# node.net
KiCad netlist of a schematic drawn in EAGLE
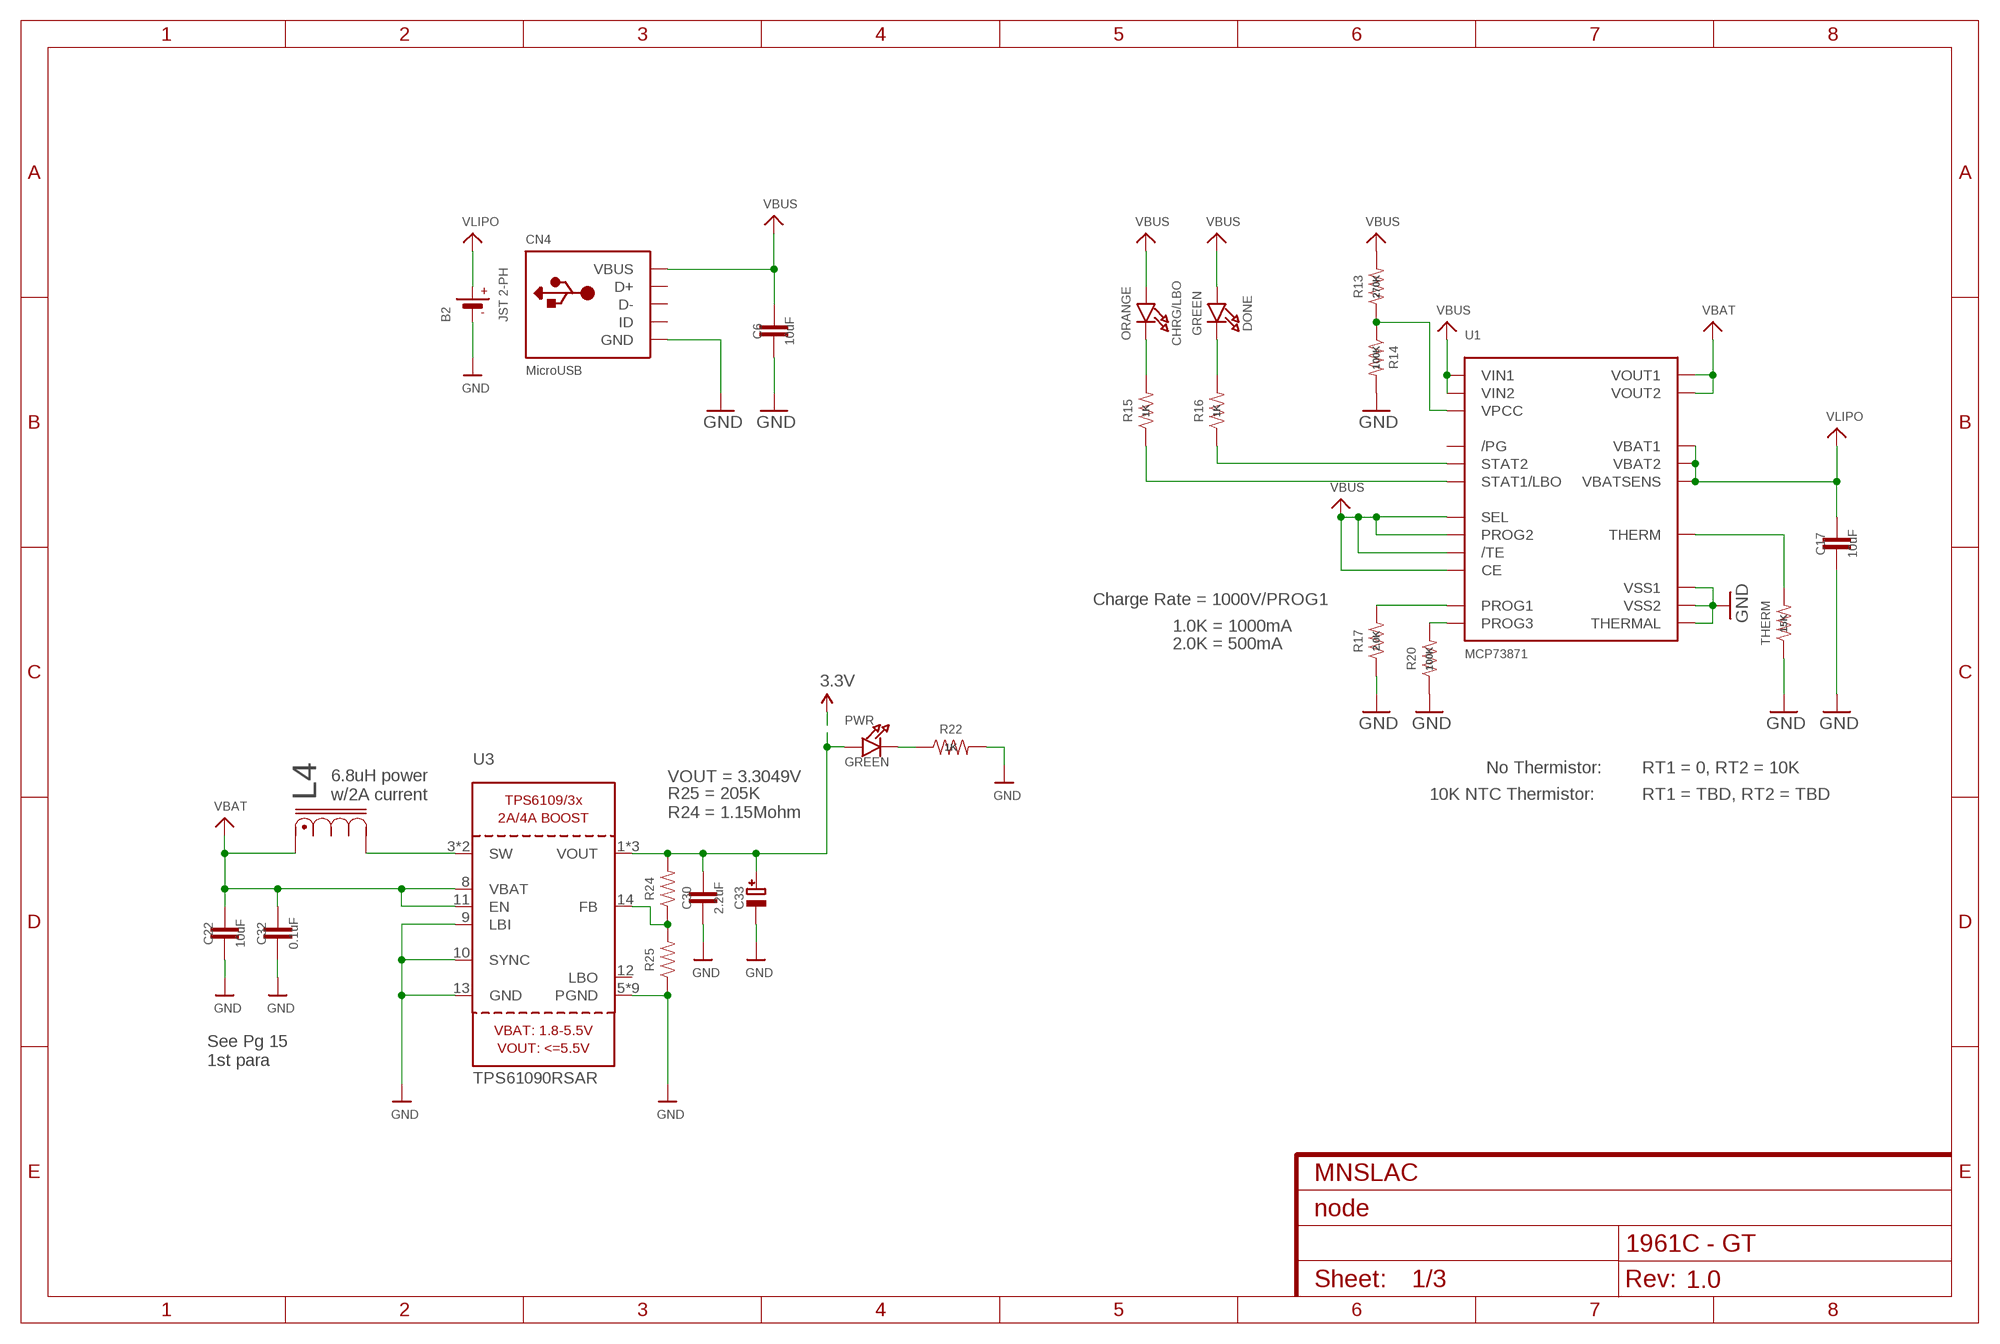
[diagram p0: schematic, sheet 1]
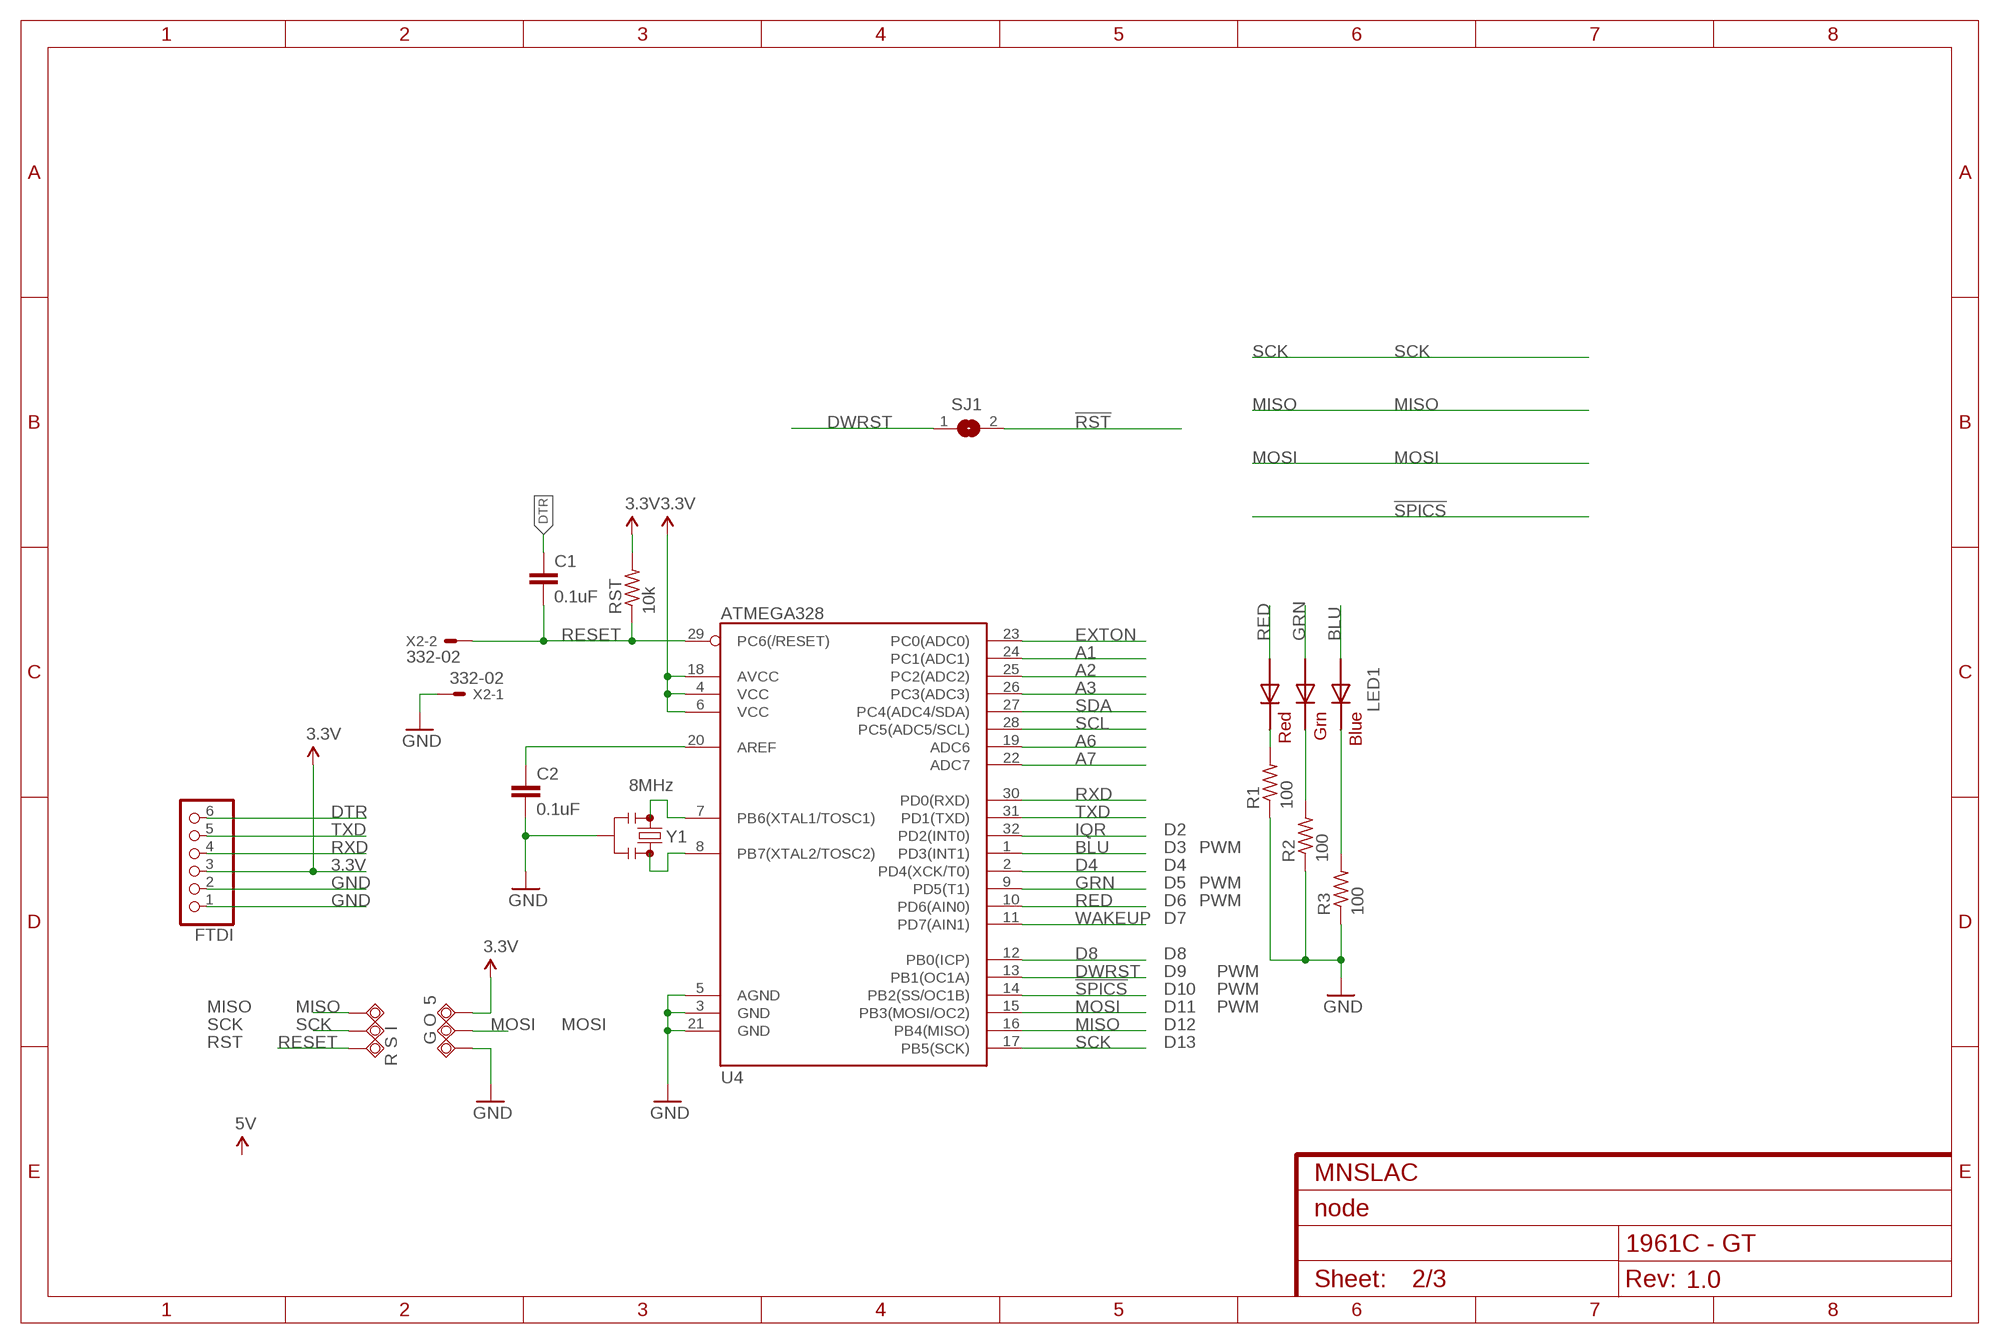
[diagram p1: schematic, sheet 2]
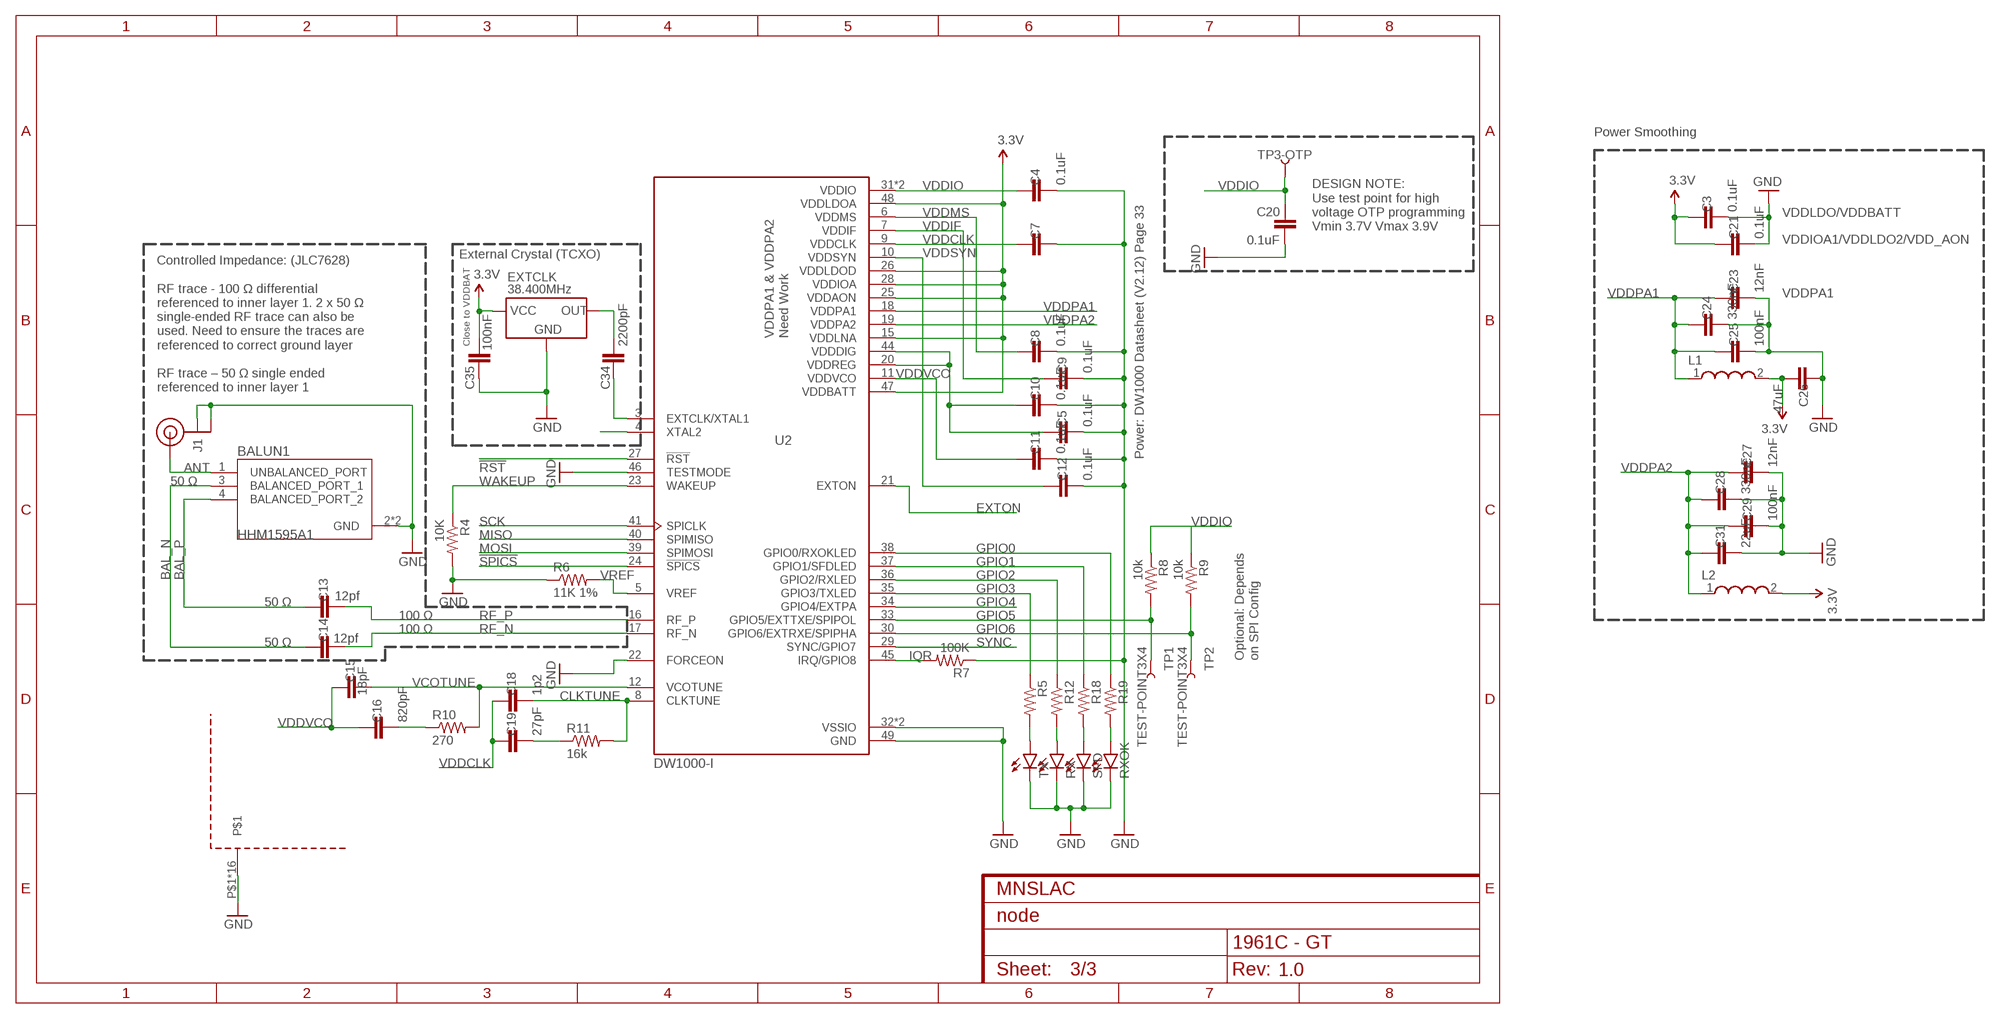
[diagram p2: schematic, sheet 3]

(export (version "E")
  (design (tool "Eeschema 10.0.6"))
  (components
    (comp (ref "BALUN1")
      (value "HHM1595A1")
      (footprint "eagle-import:BALUN_HHM1595A1")
      (fields (field (name "DIGI-KEY_PART_NUMBER") "445-3387-1-ND") (field (name "MF") "TDK"))
      (libsource (lib "eagle-import") (part "HHM1595A1"))
    )
    (comp (ref "C3")
      (value "0.1uF")
      (footprint "eagle-import:0402-CAP")
      (libsource (lib "eagle-import") (part "CAP0402-CAP"))
    )
    (comp (ref "C4")
      (value "0.1uF")
      (footprint "eagle-import:0402-CAP")
      (libsource (lib "eagle-import") (part "CAP0402-CAP"))
    )
    (comp (ref "C5")
      (value "0.1uF")
      (footprint "eagle-import:0402-CAP")
      (libsource (lib "eagle-import") (part "CAP0402-CAP"))
    )
    (comp (ref "C7")
      (value "0.1uF")
      (footprint "eagle-import:0402-CAP")
      (libsource (lib "eagle-import") (part "CAP0402-CAP"))
    )
    (comp (ref "C8")
      (value "0.1uF")
      (footprint "eagle-import:0402-CAP")
      (libsource (lib "eagle-import") (part "CAP0402-CAP"))
    )
    (comp (ref "C9")
      (value "0.1uF")
      (footprint "eagle-import:0402-CAP")
      (libsource (lib "eagle-import") (part "CAP0402-CAP"))
    )
    (comp (ref "C10")
      (value "0.1uF")
      (footprint "eagle-import:0402-CAP")
      (libsource (lib "eagle-import") (part "CAP0402-CAP"))
    )
    (comp (ref "C11")
      (value "0.1uF")
      (footprint "eagle-import:0402-CAP")
      (libsource (lib "eagle-import") (part "CAP0402-CAP"))
    )
    (comp (ref "C12")
      (value "0.1uF")
      (footprint "eagle-import:0402-CAP")
      (libsource (lib "eagle-import") (part "CAP0402-CAP"))
    )
    (comp (ref "C13")
      (value "12pf")
      (footprint "eagle-import:0402-CAP")
      (libsource (lib "eagle-import") (part "CAP0402-CAP"))
    )
    (comp (ref "C14")
      (value "12pf")
      (footprint "eagle-import:0402-CAP")
      (libsource (lib "eagle-import") (part "CAP0402-CAP"))
    )
    (comp (ref "C15")
      (value "18pF")
      (footprint "eagle-import:0402-CAP")
      (libsource (lib "eagle-import") (part "CAP0402-CAP"))
    )
    (comp (ref "C16")
      (value "820pF")
      (footprint "eagle-import:0402-CAP")
      (libsource (lib "eagle-import") (part "CAP0402-CAP"))
    )
    (comp (ref "C18")
      (value "1p2")
      (footprint "eagle-import:0402-CAP")
      (libsource (lib "eagle-import") (part "CAP0402-CAP"))
    )
    (comp (ref "C19")
      (value "27pF")
      (footprint "eagle-import:0402-CAP")
      (libsource (lib "eagle-import") (part "CAP0402-CAP"))
    )
    (comp (ref "C20")
      (value "0.1uF")
      (footprint "eagle-import:0402-CAP")
      (libsource (lib "eagle-import") (part "CAP0402-CAP"))
    )
    (comp (ref "C21")
      (value "0.1uF")
      (footprint "eagle-import:0402-CAP")
      (libsource (lib "eagle-import") (part "CAP0402-CAP"))
    )
    (comp (ref "C23")
      (value "12nF")
      (footprint "eagle-import:0402-CAP")
      (libsource (lib "eagle-import") (part "CAP0402-CAP"))
    )
    (comp (ref "C24")
      (value "330nF")
      (footprint "eagle-import:0402-CAP")
      (libsource (lib "eagle-import") (part "CAP0402-CAP"))
    )
    (comp (ref "C25")
      (value "100nF")
      (footprint "eagle-import:0402-CAP")
      (libsource (lib "eagle-import") (part "CAP0402-CAP"))
    )
    (comp (ref "C26")
      (value "47uF")
      (footprint "eagle-import:0402-CAP")
      (libsource (lib "eagle-import") (part "CAP0402-CAP"))
    )
    (comp (ref "C27")
      (value "12nF")
      (footprint "eagle-import:0402-CAP")
      (libsource (lib "eagle-import") (part "CAP0402-CAP"))
    )
    (comp (ref "C28")
      (value "330nF")
      (footprint "eagle-import:0402-CAP")
      (libsource (lib "eagle-import") (part "CAP0402-CAP"))
    )
    (comp (ref "C29")
      (value "100nF")
      (footprint "eagle-import:0402-CAP")
      (libsource (lib "eagle-import") (part "CAP0402-CAP"))
    )
    (comp (ref "C31")
      (value "22uF")
      (footprint "eagle-import:0402-CAP")
      (libsource (lib "eagle-import") (part "CAP0402-CAP"))
    )
    (comp (ref "C34")
      (value "2200pF")
      (footprint "eagle-import:0402-CAP")
      (libsource (lib "eagle-import") (part "CAP0402-CAP"))
    )
    (comp (ref "C35")
      (value "100nF")
      (footprint "eagle-import:0402-CAP")
      (libsource (lib "eagle-import") (part "CAP0402-CAP"))
    )
    (comp (ref "EXTCLK")
      (value "38.400MHz")
      (footprint "eagle-import:ASTXR-12")
      (libsource (lib "eagle-import") (part "ASTXR-12"))
    )
    (comp (ref "J1")
      (value "U.FL")
      (footprint "eagle-import:U.FL")
      (libsource (lib "eagle-import") (part "ANTENNA_U.FL"))
    )
    (comp (ref "L1")
      (value "BLM15AG601SN1D")
      (footprint "eagle-import:WE-CBA_0402(W=2.2)")
      (libsource (lib "eagle-import") (part "WE-CBA_0402(HC)"))
    )
    (comp (ref "L2")
      (value "BLM15AG601SN1D")
      (footprint "eagle-import:WE-CBA_0402(W=2.2)")
      (libsource (lib "eagle-import") (part "WE-CBA_0402(HC)"))
    )
    (comp (ref "R4")
      (value "10K")
      (footprint "eagle-import:0402-RES")
      (libsource (lib "eagle-import") (part "RESISTOR0402-RES"))
    )
    (comp (ref "R5")
      (value "470")
      (footprint "eagle-import:0402-RES")
      (libsource (lib "eagle-import") (part "RESISTOR0402-RES"))
    )
    (comp (ref "R6")
      (value "11K 1%")
      (footprint "eagle-import:0402-RES")
      (libsource (lib "eagle-import") (part "RESISTOR0402-RES"))
    )
    (comp (ref "R7")
      (value "100K")
      (footprint "eagle-import:0402-RES")
      (libsource (lib "eagle-import") (part "RESISTOR0402-RES"))
    )
    (comp (ref "R8")
      (value "10k")
      (footprint "eagle-import:0402-RES")
      (libsource (lib "eagle-import") (part "RESISTOR0402-RES"))
    )
    (comp (ref "R9")
      (value "10k")
      (footprint "eagle-import:0402-RES")
      (libsource (lib "eagle-import") (part "RESISTOR0402-RES"))
    )
    (comp (ref "R10")
      (value "270")
      (footprint "eagle-import:0402-RES")
      (libsource (lib "eagle-import") (part "RESISTOR0402-RES"))
    )
    (comp (ref "R11")
      (value "16k")
      (footprint "eagle-import:0402-RES")
      (libsource (lib "eagle-import") (part "RESISTOR0402-RES"))
    )
    (comp (ref "R12")
      (value "470")
      (footprint "eagle-import:0402-RES")
      (libsource (lib "eagle-import") (part "RESISTOR0402-RES"))
    )
    (comp (ref "R18")
      (value "470")
      (footprint "eagle-import:0402-RES")
      (libsource (lib "eagle-import") (part "RESISTOR0402-RES"))
    )
    (comp (ref "R19")
      (value "470")
      (footprint "eagle-import:0402-RES")
      (libsource (lib "eagle-import") (part "RESISTOR0402-RES"))
    )
    (comp (ref "RX")
      (value "LED0603")
      (footprint "eagle-import:LED-0603")
      (libsource (lib "eagle-import") (part "LED0603"))
    )
    (comp (ref "RXOK")
      (value "LED0603")
      (footprint "eagle-import:LED-0603")
      (libsource (lib "eagle-import") (part "LED0603"))
    )
    (comp (ref "SFD")
      (value "LED0603")
      (footprint "eagle-import:LED-0603")
      (libsource (lib "eagle-import") (part "LED0603"))
    )
    (comp (ref "TP1")
      (value "TEST-POINT3X4")
      (footprint "eagle-import:PAD.03X.04")
      (libsource (lib "eagle-import") (part "TEST-POINT3X4"))
    )
    (comp (ref "TP2")
      (value "TEST-POINT3X4")
      (footprint "eagle-import:PAD.03X.04")
      (libsource (lib "eagle-import") (part "TEST-POINT3X4"))
    )
    (comp (ref "TP3-OTP")
      (value "TEST-POINT3X4")
      (footprint "eagle-import:PAD.03X.04")
      (libsource (lib "eagle-import") (part "TEST-POINT3X4"))
    )
    (comp (ref "TX")
      (value "LED0603")
      (footprint "eagle-import:LED-0603")
      (libsource (lib "eagle-import") (part "LED0603"))
    )
    (comp (ref "U$6")
      (value "SMS-255F")
      (footprint "eagle-import:SMS-255F")
      (libsource (lib "eagle-import") (part "SMS-255F"))
    )
    (comp (ref "U2")
      (value "DW1000-I")
      (footprint "eagle-import:QFN40P600X600X90-49N")
      (fields (field (name "MF") "Decawave Limited"))
      (libsource (lib "eagle-import") (part "DW1000-I"))
    )
    (comp (ref "B2")
      (value "JST 2-PH")
      (footprint "eagle-import:JSTPH2")
      (libsource (lib "eagle-import") (part "BATTERY"))
    )
    (comp (ref "C6")
      (value "10uF")
      (footprint "eagle-import:0805")
      (libsource (lib "eagle-import") (part "CAP0805"))
    )
    (comp (ref "C17")
      (value "10uF")
      (footprint "eagle-import:0805")
      (libsource (lib "eagle-import") (part "CAP0805"))
    )
    (comp (ref "C22")
      (value "10uF")
      (footprint "eagle-import:0805")
      (libsource (lib "eagle-import") (part "CAP0805"))
    )
    (comp (ref "C30")
      (value "2.2uF")
      (footprint "eagle-import:0805")
      (libsource (lib "eagle-import") (part "CAP0805"))
    )
    (comp (ref "C32")
      (value "0.1uF")
      (footprint "eagle-import:0805")
      (libsource (lib "eagle-import") (part "CAP0805"))
    )
    (comp (ref "C33")
      (value "100uF/6V - https://www.digikey.com/product-detail/en/avx-corporation/F930G107MBA/478-8135-1-ND/4005827")
      (footprint "eagle-import:EIA3528-21_B-R")
      (libsource (lib "eagle-import") (part "CAP_TANTALUMB/3528_REFLOW"))
    )
    (comp (ref "CHRG/LBO")
      (value "ORANGE")
      (footprint "eagle-import:CHIPLED_0805_NOOUTLINE")
      (libsource (lib "eagle-import") (part "LED0805_NOOUTLINE"))
    )
    (comp (ref "CN4")
      (value "MicroUSB")
      (footprint "eagle-import:4UCONN_20329")
      (libsource (lib "eagle-import") (part "USBMICRO_20329"))
    )
    (comp (ref "DONE")
      (value "GREEN")
      (footprint "eagle-import:CHIPLED_0805_NOOUTLINE")
      (libsource (lib "eagle-import") (part "LED0805_NOOUTLINE"))
    )
    (comp (ref "L4")
      (value "https://www.digikey.com/product-detail/en/eaton-electronics-division/DR73-6R8-R/513-1134-1-ND/754632")
      (footprint "eagle-import:DR73")
      (fields (field (name "MANUFACTURER_PART_NUMBER") "DR736R8R"))
      (libsource (lib "eagle-import") (part "DR73-6R8-R"))
    )
    (comp (ref "PWR")
      (value "GREEN")
      (footprint "eagle-import:CHIPLED_0805_NOOUTLINE")
      (libsource (lib "eagle-import") (part "LED0805_NOOUTLINE"))
    )
    (comp (ref "R13")
      (value "270K")
      (footprint "eagle-import:0805")
      (libsource (lib "eagle-import") (part "RESISTOR0805-RES"))
    )
    (comp (ref "R14")
      (value "100K")
      (footprint "eagle-import:0805")
      (libsource (lib "eagle-import") (part "RESISTOR0805-RES"))
    )
    (comp (ref "R15")
      (value "1K")
      (footprint "eagle-import:0805")
      (libsource (lib "eagle-import") (part "RESISTOR0805-RES"))
    )
    (comp (ref "R16")
      (value "1K")
      (footprint "eagle-import:0805")
      (libsource (lib "eagle-import") (part "RESISTOR0805-RES"))
    )
    (comp (ref "R17")
      (value "2.0K")
      (footprint "eagle-import:0805")
      (libsource (lib "eagle-import") (part "RESISTOR0805-RES"))
    )
    (comp (ref "R20")
      (value "100K")
      (footprint "eagle-import:0805")
      (libsource (lib "eagle-import") (part "RESISTOR0805-RES"))
    )
    (comp (ref "R22")
      (value "1K")
      (footprint "eagle-import:0805")
      (libsource (lib "eagle-import") (part "RESISTOR0805-RES"))
    )
    (comp (ref "R24")
      (value "1.15M")
      (footprint "eagle-import:0805")
      (libsource (lib "eagle-import") (part "RESISTOR0805-RES"))
    )
    (comp (ref "R25")
      (value "205K")
      (footprint "eagle-import:0805")
      (libsource (lib "eagle-import") (part "RESISTOR0805-RES"))
    )
    (comp (ref "THERM")
      (value "15K")
      (footprint "eagle-import:0805")
      (libsource (lib "eagle-import") (part "RESISTOR0805-RES"))
    )
    (comp (ref "U1")
      (value "MCP73871")
      (footprint "eagle-import:QFN20_4MM")
      (libsource (lib "eagle-import") (part "MCP73871"))
    )
    (comp (ref "U3")
      (value "TPS61090RSAR")
      (footprint "eagle-import:PVQFN-16")
      (libsource (lib "eagle-import") (part "VREG_TPS6103X"))
    )
    (comp (ref "5")
      (value "TPSQTP08R")
      (footprint "eagle-import:TP08R")
      (libsource (lib "eagle-import") (part "TPSQTP08R"))
    )
    (comp (ref "C1")
      (value "0.1uF")
      (footprint "eagle-import:0805-CAP")
      (libsource (lib "eagle-import") (part "1.0UF-25V-+80/-20(0805){dblquote}"))
    )
    (comp (ref "C2")
      (value "0.1uF")
      (footprint "eagle-import:0805-CAP")
      (libsource (lib "eagle-import") (part "1.0UF-25V-+80/-20(0805){dblquote}"))
    )
    (comp (ref "FTDI")
      (value "PINHD-1X6LOCK")
      (footprint "eagle-import:1X06-BIGLOCK")
      (libsource (lib "eagle-import") (part "PINHD-1X6LOCK"))
    )
    (comp (ref "G")
      (value "TPSQTP08R")
      (footprint "eagle-import:TP08R")
      (libsource (lib "eagle-import") (part "TPSQTP08R"))
    )
    (comp (ref "I")
      (value "TPSQTP08R")
      (footprint "eagle-import:TP08R")
      (libsource (lib "eagle-import") (part "TPSQTP08R"))
    )
    (comp (ref "LED1")
      (value "RGBLED5050")
      (footprint "eagle-import:RGBLED5050")
      (libsource (lib "eagle-import") (part "RGBLED5050"))
    )
    (comp (ref "O")
      (value "TPSQTP08R")
      (footprint "eagle-import:TP08R")
      (libsource (lib "eagle-import") (part "TPSQTP08R"))
    )
    (comp (ref "R")
      (value "TPSQTP08R")
      (footprint "eagle-import:TP08R")
      (libsource (lib "eagle-import") (part "TPSQTP08R"))
    )
    (comp (ref "R1")
      (value "100")
      (footprint "eagle-import:R0805")
      (libsource (lib "eagle-import") (part "R-US_R0805"))
    )
    (comp (ref "R2")
      (value "100")
      (footprint "eagle-import:R0805")
      (libsource (lib "eagle-import") (part "R-US_R0805"))
    )
    (comp (ref "R3")
      (value "100")
      (footprint "eagle-import:R0805")
      (libsource (lib "eagle-import") (part "R-US_R0805"))
    )
    (comp (ref "RST")
      (value "10k")
      (footprint "eagle-import:R0805")
      (libsource (lib "eagle-import") (part "R-US_R0805"))
    )
    (comp (ref "S")
      (value "TPSQTP08R")
      (footprint "eagle-import:TP08R")
      (libsource (lib "eagle-import") (part "TPSQTP08R"))
    )
    (comp (ref "SJ1") (value "SJ") (footprint "eagle-import:SJ") (libsource (lib "eagle-import") (part "SJ")))
    (comp (ref "U4")
      (value "ATMEGA328")
      (footprint "eagle-import:TQFP32-08")
      (libsource (lib "eagle-import") (part "ATMEGA168"))
    )
    (comp (ref "X2")
      (value "332-02")
      (footprint "eagle-import:332-02")
      (libsource (lib "eagle-import") (part "332-02"))
    )
    (comp (ref "Y1")
      (value "8MHz")
      (footprint "eagle-import:RESONATOR-SMD_MED")
      (libsource (lib "eagle-import") (part "RESONATOR4MHZ"))
    )
  )
  (nets
    (net (code "1") (name "3.3V") (class "Default")
      (node (ref "5") (pin "TP") (pinfunction "TP_TP") (pintype "input"))
      (node (ref "C21") (pin "1") (pinfunction "1_1") (pintype "passive"))
      (node (ref "C26") (pin "2") (pinfunction "2_2") (pintype "passive"))
      (node (ref "C3") (pin "1") (pinfunction "1_1") (pintype "passive"))
      (node (ref "C30") (pin "1") (pinfunction "1_1") (pintype "passive"))
      (node (ref "C33") (pin "+") (pinfunction "+_+") (pintype "passive"))
      (node (ref "C35") (pin "2") (pinfunction "2_2") (pintype "passive"))
      (node (ref "EXTCLK") (pin "P$6") (pinfunction "VCC_P$6") (pintype "bidirectional"))
      (node (ref "FTDI") (pin "3") (pinfunction "3_3") (pintype "passive"))
      (node (ref "L1") (pin "2") (pinfunction "2_2") (pintype "passive"))
      (node (ref "L2") (pin "2") (pinfunction "2_2") (pintype "passive"))
      (node (ref "PWR") (pin "A") (pinfunction "A_A") (pintype "passive"))
      (node (ref "R24") (pin "2") (pinfunction "2_2") (pintype "passive"))
      (node (ref "RST") (pin "2") (pinfunction "2_2") (pintype "passive"))
      (node (ref "U2") (pin "15") (pinfunction "VDDLNA_15") (pintype "power_in"))
      (node (ref "U2") (pin "25") (pinfunction "VDDAON_25") (pintype "power_in"))
      (node (ref "U2") (pin "26") (pinfunction "VDDLDOD_26") (pintype "power_in"))
      (node (ref "U2") (pin "28") (pinfunction "VDDIOA_28") (pintype "power_in"))
      (node (ref "U2") (pin "47") (pinfunction "VDDBATT_47") (pintype "power_in"))
      (node (ref "U2") (pin "48") (pinfunction "VDDLDOA_48") (pintype "power_in"))
      (node (ref "U3") (pin "1") (pinfunction "VOUT_1") (pintype "power_in"))
      (node (ref "U3") (pin "15") (pinfunction "VOUT_15") (pintype "power_in"))
      (node (ref "U3") (pin "16") (pinfunction "VOUT_16") (pintype "power_in"))
      (node (ref "U4") (pin "18") (pinfunction "AVCC_18") (pintype "bidirectional"))
      (node (ref "U4") (pin "4") (pinfunction "VCC_4") (pintype "bidirectional"))
      (node (ref "U4") (pin "6") (pinfunction "VCC_6") (pintype "bidirectional"))
    )
    (net (code "3") (name "A1") (class "Default")
      (node (ref "U4") (pin "24") (pinfunction "PC1(ADC1)_24") (pintype "bidirectional"))
    )
    (net (code "4") (name "A2") (class "Default")
      (node (ref "U4") (pin "25") (pinfunction "PC2(ADC2)_25") (pintype "bidirectional"))
    )
    (net (code "5") (name "A3") (class "Default")
      (node (ref "U4") (pin "26") (pinfunction "PC3(ADC3)_26") (pintype "bidirectional"))
    )
    (net (code "6") (name "A6") (class "Default")
      (node (ref "U4") (pin "19") (pinfunction "ADC6_19") (pintype "bidirectional"))
    )
    (net (code "7") (name "A7") (class "Default")
      (node (ref "U4") (pin "22") (pinfunction "ADC7_22") (pintype "bidirectional"))
    )
    (net (code "8") (name "ANT") (class "Default")
      (node (ref "BALUN1") (pin "1") (pinfunction "UNBALANCED_PORT_1") (pintype "bidirectional"))
      (node (ref "J1") (pin "3") (pinfunction "SIGNAL_3") (pintype "passive"))
    )
    (net (code "9") (name "BAL_N") (class "Default")
      (node (ref "BALUN1") (pin "3") (pinfunction "BALANCED_PORT_1_3") (pintype "bidirectional"))
      (node (ref "C14") (pin "1") (pinfunction "1_1") (pintype "passive"))
    )
    (net (code "10") (name "BAL_P") (class "Default")
      (node (ref "BALUN1") (pin "4") (pinfunction "BALANCED_PORT_2_4") (pintype "bidirectional"))
      (node (ref "C13") (pin "1") (pinfunction "1_1") (pintype "passive"))
    )
    (net (code "11") (name "BLU") (class "Default")
      (node (ref "LED1") (pin "3") (pinfunction "BLUE_A_3") (pintype "bidirectional"))
      (node (ref "U4") (pin "1") (pinfunction "PD3(INT1)_1") (pintype "bidirectional"))
    )
    (net (code "12") (name "CLKTUNE") (class "Default")
      (node (ref "C18") (pin "2") (pinfunction "2_2") (pintype "passive"))
      (node (ref "R11") (pin "2") (pinfunction "2_2") (pintype "passive"))
      (node (ref "U2") (pin "8") (pinfunction "CLKTUNE_8") (pintype "bidirectional"))
    )
    (net (code "13") (name "D4") (class "Default")
      (node (ref "U4") (pin "2") (pinfunction "PD4(XCK/T0)_2") (pintype "bidirectional"))
    )
    (net (code "14") (name "D8") (class "Default")
      (node (ref "U4") (pin "12") (pinfunction "PB0(ICP)_12") (pintype "bidirectional"))
    )
    (net (code "15") (name "DTR") (class "Default")
      (node (ref "C1") (pin "1") (pinfunction "1_1") (pintype "passive"))
      (node (ref "FTDI") (pin "6") (pinfunction "6_6") (pintype "passive"))
    )
    (net (code "16") (name "DWRST") (class "Default")
      (node (ref "SJ1") (pin "1") (pinfunction "1_1") (pintype "passive"))
      (node (ref "U4") (pin "13") (pinfunction "PB1(OC1A)_13") (pintype "bidirectional"))
    )
    (net (code "17") (name "EXTON") (class "Default")
      (node (ref "U2") (pin "21") (pinfunction "EXTON_21") (pintype "output"))
      (node (ref "U4") (pin "23") (pinfunction "PC0(ADC0)_23") (pintype "bidirectional"))
    )
    (net (code "18") (name "GND") (class "Default")
      (node (ref "B2") (pin "1") (pinfunction "-_1") (pintype "passive"))
      (node (ref "BALUN1") (pin "2") (pinfunction "GND_2") (pintype "power_in"))
      (node (ref "BALUN1") (pin "5") (pinfunction "GND_5") (pintype "power_in"))
      (node (ref "C10") (pin "2") (pinfunction "2_2") (pintype "passive"))
      (node (ref "C11") (pin "2") (pinfunction "2_2") (pintype "passive"))
      (node (ref "C12") (pin "2") (pinfunction "2_2") (pintype "passive"))
      (node (ref "C17") (pin "2") (pinfunction "2_2") (pintype "passive"))
      (node (ref "C2") (pin "2") (pinfunction "2_2") (pintype "passive"))
      (node (ref "C20") (pin "1") (pinfunction "1_1") (pintype "passive"))
      (node (ref "C21") (pin "2") (pinfunction "2_2") (pintype "passive"))
      (node (ref "C22") (pin "2") (pinfunction "2_2") (pintype "passive"))
      (node (ref "C23") (pin "2") (pinfunction "2_2") (pintype "passive"))
      (node (ref "C24") (pin "2") (pinfunction "2_2") (pintype "passive"))
      (node (ref "C25") (pin "2") (pinfunction "2_2") (pintype "passive"))
      (node (ref "C26") (pin "1") (pinfunction "1_1") (pintype "passive"))
      (node (ref "C27") (pin "2") (pinfunction "2_2") (pintype "passive"))
      (node (ref "C28") (pin "2") (pinfunction "2_2") (pintype "passive"))
      (node (ref "C29") (pin "2") (pinfunction "2_2") (pintype "passive"))
      (node (ref "C3") (pin "2") (pinfunction "2_2") (pintype "passive"))
      (node (ref "C30") (pin "2") (pinfunction "2_2") (pintype "passive"))
      (node (ref "C31") (pin "2") (pinfunction "2_2") (pintype "passive"))
      (node (ref "C32") (pin "2") (pinfunction "2_2") (pintype "passive"))
      (node (ref "C33") (pin "-") (pinfunction "-_-") (pintype "passive"))
      (node (ref "C35") (pin "1") (pinfunction "1_1") (pintype "passive"))
      (node (ref "C4") (pin "2") (pinfunction "2_2") (pintype "passive"))
      (node (ref "C5") (pin "2") (pinfunction "2_2") (pintype "passive"))
      (node (ref "C6") (pin "2") (pinfunction "2_2") (pintype "passive"))
      (node (ref "C7") (pin "2") (pinfunction "2_2") (pintype "passive"))
      (node (ref "C8") (pin "2") (pinfunction "2_2") (pintype "passive"))
      (node (ref "C9") (pin "2") (pinfunction "2_2") (pintype "passive"))
      (node (ref "CN4") (pin "BASE@1") (pinfunction "GND_BASE@1") (pintype "power_in"))
      (node (ref "CN4") (pin "BASE@2") (pinfunction "GND_BASE@2") (pintype "power_in"))
      (node (ref "CN4") (pin "GND") (pinfunction "GND_GND") (pintype "power_in"))
      (node (ref "CN4") (pin "SPRT@1") (pinfunction "GND_SPRT@1") (pintype "power_in"))
      (node (ref "CN4") (pin "SPRT@2") (pinfunction "GND_SPRT@2") (pintype "power_in"))
      (node (ref "CN4") (pin "SPRT@3") (pinfunction "GND_SPRT@3") (pintype "power_in"))
      (node (ref "CN4") (pin "SPRT@4") (pinfunction "GND_SPRT@4") (pintype "power_in"))
      (node (ref "EXTCLK") (pin "P$1") (pinfunction "GND_P$1") (pintype "bidirectional"))
      (node (ref "EXTCLK") (pin "P$3") (pinfunction "GND_P$3") (pintype "bidirectional"))
      (node (ref "FTDI") (pin "1") (pinfunction "1_1") (pintype "passive"))
      (node (ref "FTDI") (pin "2") (pinfunction "2_2") (pintype "passive"))
      (node (ref "G") (pin "TP") (pinfunction "TP_TP") (pintype "input"))
      (node (ref "J1") (pin "1") (pinfunction "GND_1") (pintype "passive"))
      (node (ref "J1") (pin "2") (pinfunction "GND_2") (pintype "passive"))
      (node (ref "R1") (pin "1") (pinfunction "1_1") (pintype "passive"))
      (node (ref "R14") (pin "2") (pinfunction "2_2") (pintype "passive"))
      (node (ref "R17") (pin "1") (pinfunction "1_1") (pintype "passive"))
      (node (ref "R2") (pin "1") (pinfunction "1_1") (pintype "passive"))
      (node (ref "R20") (pin "1") (pinfunction "1_1") (pintype "passive"))
      (node (ref "R22") (pin "2") (pinfunction "2_2") (pintype "passive"))
      (node (ref "R25") (pin "1") (pinfunction "1_1") (pintype "passive"))
      (node (ref "R3") (pin "1") (pinfunction "1_1") (pintype "passive"))
      (node (ref "R4") (pin "2") (pinfunction "2_2") (pintype "passive"))
      (node (ref "R6") (pin "1") (pinfunction "1_1") (pintype "passive"))
      (node (ref "R7") (pin "1") (pinfunction "1_1") (pintype "passive"))
      (node (ref "RX") (pin "C") (pinfunction "C_C") (pintype "passive"))
      (node (ref "RXOK") (pin "C") (pinfunction "C_C") (pintype "passive"))
      (node (ref "SFD") (pin "C") (pinfunction "C_C") (pintype "passive"))
      (node (ref "THERM") (pin "1") (pinfunction "1_1") (pintype "passive"))
      (node (ref "TX") (pin "C") (pinfunction "C_C") (pintype "passive"))
      (node (ref "U$6") (pin "P$1") (pinfunction "P$1_P$1") (pintype "bidirectional"))
      (node (ref "U$6") (pin "P$10") (pinfunction "P$1_P$10") (pintype "bidirectional"))
      (node (ref "U$6") (pin "P$11") (pinfunction "P$1_P$11") (pintype "bidirectional"))
      (node (ref "U$6") (pin "P$12") (pinfunction "P$1_P$12") (pintype "bidirectional"))
      (node (ref "U$6") (pin "P$13") (pinfunction "P$1_P$13") (pintype "bidirectional"))
      (node (ref "U$6") (pin "P$14") (pinfunction "P$1_P$14") (pintype "bidirectional"))
      (node (ref "U$6") (pin "P$15") (pinfunction "P$1_P$15") (pintype "bidirectional"))
      (node (ref "U$6") (pin "P$16") (pinfunction "P$1_P$16") (pintype "bidirectional"))
      (node (ref "U$6") (pin "P$2") (pinfunction "P$1_P$2") (pintype "bidirectional"))
      (node (ref "U$6") (pin "P$3") (pinfunction "P$1_P$3") (pintype "bidirectional"))
      (node (ref "U$6") (pin "P$4") (pinfunction "P$1_P$4") (pintype "bidirectional"))
      (node (ref "U$6") (pin "P$5") (pinfunction "P$1_P$5") (pintype "bidirectional"))
      (node (ref "U$6") (pin "P$6") (pinfunction "P$1_P$6") (pintype "bidirectional"))
      (node (ref "U$6") (pin "P$7") (pinfunction "P$1_P$7") (pintype "bidirectional"))
      (node (ref "U$6") (pin "P$8") (pinfunction "P$1_P$8") (pintype "bidirectional"))
      (node (ref "U$6") (pin "P$9") (pinfunction "P$1_P$9") (pintype "bidirectional"))
      (node (ref "U1") (pin "P$10") (pinfunction "VSS1_P$10") (pintype "bidirectional"))
      (node (ref "U1") (pin "P$11") (pinfunction "VSS2_P$11") (pintype "bidirectional"))
      (node (ref "U1") (pin "P$21") (pinfunction "THERMAL_P$21") (pintype "bidirectional"))
      (node (ref "U2") (pin "22") (pinfunction "FORCEON_22") (pintype "bidirectional"))
      (node (ref "U2") (pin "32") (pinfunction "VSSIO_32") (pintype "power_in"))
      (node (ref "U2") (pin "43") (pinfunction "VSSIO_43") (pintype "power_in"))
      (node (ref "U2") (pin "46") (pinfunction "TESTMODE_46") (pintype "input"))
      (node (ref "U2") (pin "49") (pinfunction "GND_49") (pintype "power_in"))
      (node (ref "U3") (pin "10") (pinfunction "SYNC_10") (pintype "input"))
      (node (ref "U3") (pin "13") (pinfunction "GND_13") (pintype "power_in"))
      (node (ref "U3") (pin "5") (pinfunction "PGND_5") (pintype "power_in"))
      (node (ref "U3") (pin "6") (pinfunction "PGND_6") (pintype "power_in"))
      (node (ref "U3") (pin "7") (pinfunction "PGND_7") (pintype "power_in"))
      (node (ref "U3") (pin "9") (pinfunction "LBI_9") (pintype "input"))
      (node (ref "U3") (pin "P$18") (pinfunction "PGND_P$18") (pintype "power_in"))
      (node (ref "U3") (pin "P$19") (pinfunction "PGND_P$19") (pintype "power_in"))
      (node (ref "U3") (pin "P$20") (pinfunction "PGND_P$20") (pintype "power_in"))
      (node (ref "U3") (pin "P$21") (pinfunction "PGND_P$21") (pintype "power_in"))
      (node (ref "U3") (pin "P$22") (pinfunction "PGND_P$22") (pintype "power_in"))
      (node (ref "U3") (pin "THERMAL") (pinfunction "PGND_THERMAL") (pintype "power_in"))
      (node (ref "U4") (pin "21") (pinfunction "GND_21") (pintype "bidirectional"))
      (node (ref "U4") (pin "3") (pinfunction "GND_3") (pintype "bidirectional"))
      (node (ref "U4") (pin "5") (pinfunction "AGND_5") (pintype "bidirectional"))
      (node (ref "X2") (pin "1") (pinfunction "S_1") (pintype "passive"))
      (node (ref "Y1") (pin "2") (pinfunction "2_2") (pintype "passive"))
    )
    (net (code "19") (name "GPIO0") (class "Default")
      (node (ref "R19") (pin "1") (pinfunction "1_1") (pintype "passive"))
      (node (ref "U2") (pin "38") (pinfunction "GPIO0/RXOKLED_38") (pintype "bidirectional"))
    )
    (net (code "20") (name "GPIO1") (class "Default")
      (node (ref "R18") (pin "1") (pinfunction "1_1") (pintype "passive"))
      (node (ref "U2") (pin "37") (pinfunction "GPIO1/SFDLED_37") (pintype "bidirectional"))
    )
    (net (code "21") (name "GPIO2") (class "Default")
      (node (ref "R12") (pin "1") (pinfunction "1_1") (pintype "passive"))
      (node (ref "U2") (pin "36") (pinfunction "GPIO2/RXLED_36") (pintype "bidirectional"))
    )
    (net (code "22") (name "GPIO3") (class "Default")
      (node (ref "R5") (pin "1") (pinfunction "1_1") (pintype "passive"))
      (node (ref "U2") (pin "35") (pinfunction "GPIO3/TXLED_35") (pintype "bidirectional"))
    )
    (net (code "23") (name "GPIO4") (class "Default")
      (node (ref "U2") (pin "34") (pinfunction "GPIO4/EXTPA_34") (pintype "bidirectional"))
    )
    (net (code "24") (name "GPIO5") (class "Default")
      (node (ref "R8") (pin "2") (pinfunction "2_2") (pintype "passive"))
      (node (ref "TP1") (pin "P$1") (pinfunction "1_P$1") (pintype "bidirectional"))
      (node (ref "U2") (pin "33") (pinfunction "GPIO5/EXTTXE/SPIPOL_33") (pintype "bidirectional"))
    )
    (net (code "25") (name "GPIO6") (class "Default")
      (node (ref "R9") (pin "2") (pinfunction "2_2") (pintype "passive"))
      (node (ref "TP2") (pin "P$1") (pinfunction "1_P$1") (pintype "bidirectional"))
      (node (ref "U2") (pin "30") (pinfunction "GPIO6/EXTRXE/SPIPHA_30") (pintype "bidirectional"))
    )
    (net (code "26") (name "GRN") (class "Default")
      (node (ref "LED1") (pin "1") (pinfunction "GREEN_A_1") (pintype "bidirectional"))
      (node (ref "U4") (pin "9") (pinfunction "PD5(T1)_9") (pintype "bidirectional"))
    )
    (net (code "27") (name "IQR") (class "Default")
      (node (ref "R7") (pin "2") (pinfunction "2_2") (pintype "passive"))
      (node (ref "U2") (pin "45") (pinfunction "IRQ/GPIO8_45") (pintype "bidirectional"))
      (node (ref "U4") (pin "32") (pinfunction "PD2(INT0)_32") (pintype "bidirectional"))
    )
    (net (code "28") (name "MISO") (class "Default")
      (node (ref "I") (pin "TP") (pinfunction "TP_TP") (pintype "input"))
      (node (ref "U2") (pin "40") (pinfunction "SPIMISO_40") (pintype "output"))
      (node (ref "U4") (pin "16") (pinfunction "PB4(MISO)_16") (pintype "bidirectional"))
    )
    (net (code "29") (name "MOSI") (class "Default")
      (node (ref "O") (pin "TP") (pinfunction "TP_TP") (pintype "input"))
      (node (ref "U2") (pin "39") (pinfunction "SPIMOSI_39") (pintype "input"))
      (node (ref "U4") (pin "15") (pinfunction "PB3(MOSI/OC2)_15") (pintype "bidirectional"))
    )
    (net (code "30") (name "Net-(C16-Pad2)") (class "Default")
      (node (ref "C16") (pin "2") (pinfunction "2_2") (pintype "passive"))
      (node (ref "R10") (pin "1") (pinfunction "1_1") (pintype "passive"))
    )
    (net (code "31") (name "Net-(C19-Pad2)") (class "Default")
      (node (ref "C19") (pin "2") (pinfunction "2_2") (pintype "passive"))
      (node (ref "R11") (pin "1") (pinfunction "1_1") (pintype "passive"))
    )
    (net (code "32") (name "Net-(CHRG/LBO-PadC)") (class "Default")
      (node (ref "CHRG/LBO") (pin "C") (pinfunction "C_C") (pintype "passive"))
      (node (ref "R15") (pin "2") (pinfunction "2_2") (pintype "passive"))
    )
    (net (code "33") (name "Net-(DONE-PadC)") (class "Default")
      (node (ref "DONE") (pin "C") (pinfunction "C_C") (pintype "passive"))
      (node (ref "R16") (pin "2") (pinfunction "2_2") (pintype "passive"))
    )
    (net (code "34") (name "Net-(EXTCLK-OUT)") (class "Default")
      (node (ref "C34") (pin "2") (pinfunction "2_2") (pintype "passive"))
      (node (ref "EXTCLK") (pin "P$4") (pinfunction "OUT_P$4") (pintype "bidirectional"))
    )
    (net (code "35") (name "Net-(L4-Pad2)") (class "Default")
      (node (ref "L4") (pin "2") (pinfunction "2_2") (pintype "passive"))
      (node (ref "U3") (pin "3") (pinfunction "SW_3") (pintype "input"))
      (node (ref "U3") (pin "4") (pinfunction "SW_4") (pintype "input"))
    )
    (net (code "36") (name "Net-(LED1-BLUE_C)") (class "Default")
      (node (ref "LED1") (pin "4") (pinfunction "BLUE_C_4") (pintype "bidirectional"))
      (node (ref "R3") (pin "2") (pinfunction "2_2") (pintype "passive"))
    )
    (net (code "37") (name "Net-(LED1-GREEN_C)") (class "Default")
      (node (ref "LED1") (pin "6") (pinfunction "GREEN_C_6") (pintype "bidirectional"))
      (node (ref "R2") (pin "2") (pinfunction "2_2") (pintype "passive"))
    )
    (net (code "38") (name "Net-(LED1-RED_C)") (class "Default")
      (node (ref "LED1") (pin "5") (pinfunction "RED_C_5") (pintype "bidirectional"))
      (node (ref "R1") (pin "2") (pinfunction "2_2") (pintype "passive"))
    )
    (net (code "39") (name "Net-(PWR-PadC)") (class "Default")
      (node (ref "PWR") (pin "C") (pinfunction "C_C") (pintype "passive"))
      (node (ref "R22") (pin "1") (pinfunction "1_1") (pintype "passive"))
    )
    (net (code "40") (name "Net-(R5-Pad2)") (class "Default")
      (node (ref "R5") (pin "2") (pinfunction "2_2") (pintype "passive"))
      (node (ref "TX") (pin "A") (pinfunction "A_A") (pintype "passive"))
    )
    (net (code "41") (name "Net-(R12-Pad2)") (class "Default")
      (node (ref "R12") (pin "2") (pinfunction "2_2") (pintype "passive"))
      (node (ref "RX") (pin "A") (pinfunction "A_A") (pintype "passive"))
    )
    (net (code "42") (name "Net-(R18-Pad2)") (class "Default")
      (node (ref "R18") (pin "2") (pinfunction "2_2") (pintype "passive"))
      (node (ref "SFD") (pin "A") (pinfunction "A_A") (pintype "passive"))
    )
    (net (code "43") (name "Net-(R19-Pad2)") (class "Default")
      (node (ref "R19") (pin "2") (pinfunction "2_2") (pintype "passive"))
      (node (ref "RXOK") (pin "A") (pinfunction "A_A") (pintype "passive"))
    )
    (net (code "44") (name "Net-(U1-PROG1)") (class "Default")
      (node (ref "R17") (pin "2") (pinfunction "2_2") (pintype "passive"))
      (node (ref "U1") (pin "P$13") (pinfunction "PROG1_P$13") (pintype "bidirectional"))
    )
    (net (code "45") (name "Net-(U1-PROG3)") (class "Default")
      (node (ref "R20") (pin "2") (pinfunction "2_2") (pintype "passive"))
      (node (ref "U1") (pin "P$12") (pinfunction "PROG3_P$12") (pintype "bidirectional"))
    )
    (net (code "46") (name "Net-(U1-STAT1{slash}LBO)") (class "Default")
      (node (ref "R15") (pin "1") (pinfunction "1_1") (pintype "passive"))
      (node (ref "U1") (pin "P$8") (pinfunction "STAT1/LBO_P$8") (pintype "bidirectional"))
    )
    (net (code "47") (name "Net-(U1-STAT2)") (class "Default")
      (node (ref "R16") (pin "1") (pinfunction "1_1") (pintype "passive"))
      (node (ref "U1") (pin "P$7") (pinfunction "STAT2_P$7") (pintype "bidirectional"))
    )
    (net (code "48") (name "Net-(U1-THERM)") (class "Default")
      (node (ref "THERM") (pin "2") (pinfunction "2_2") (pintype "passive"))
      (node (ref "U1") (pin "P$5") (pinfunction "THERM_P$5") (pintype "bidirectional"))
    )
    (net (code "49") (name "Net-(U1-VPCC)") (class "Default")
      (node (ref "R13") (pin "1") (pinfunction "1_1") (pintype "passive"))
      (node (ref "R14") (pin "1") (pinfunction "1_1") (pintype "passive"))
      (node (ref "U1") (pin "P$2") (pinfunction "VPCC_P$2") (pintype "bidirectional"))
    )
    (net (code "50") (name "Net-(U2-EXTCLK{slash}XTAL1)") (class "Default")
      (node (ref "C34") (pin "1") (pinfunction "1_1") (pintype "passive"))
      (node (ref "U2") (pin "3") (pinfunction "EXTCLK/XTAL1_3") (pintype "input"))
    )
    (net (code "51") (name "Net-(U2-VDDDIG)") (class "Default")
      (node (ref "C10") (pin "1") (pinfunction "1_1") (pintype "passive"))
      (node (ref "C5") (pin "1") (pinfunction "1_1") (pintype "passive"))
      (node (ref "U2") (pin "20") (pinfunction "VDDREG_20") (pintype "power_in"))
      (node (ref "U2") (pin "44") (pinfunction "VDDDIG_44") (pintype "power_in"))
    )
    (net (code "52") (name "Net-(U3-FB)") (class "Default")
      (node (ref "R24") (pin "1") (pinfunction "1_1") (pintype "passive"))
      (node (ref "R25") (pin "2") (pinfunction "2_2") (pintype "passive"))
      (node (ref "U3") (pin "14") (pinfunction "FB_14") (pintype "input"))
    )
    (net (code "53") (name "Net-(U4-AREF)") (class "Default")
      (node (ref "C2") (pin "1") (pinfunction "1_1") (pintype "passive"))
      (node (ref "U4") (pin "20") (pinfunction "AREF_20") (pintype "bidirectional"))
    )
    (net (code "54") (name "Net-(U4-PB6(XTAL1{slash}TOSC1))") (class "Default")
      (node (ref "U4") (pin "7") (pinfunction "PB6(XTAL1/TOSC1)_7") (pintype "bidirectional"))
      (node (ref "Y1") (pin "1") (pinfunction "1_1") (pintype "passive"))
    )
    (net (code "55") (name "Net-(U4-PB7(XTAL2{slash}TOSC2))") (class "Default")
      (node (ref "U4") (pin "8") (pinfunction "PB7(XTAL2/TOSC2)_8") (pintype "bidirectional"))
      (node (ref "Y1") (pin "3") (pinfunction "3_3") (pintype "passive"))
    )
    (net (code "56") (name "RED") (class "Default")
      (node (ref "LED1") (pin "2") (pinfunction "RED_A_2") (pintype "bidirectional"))
      (node (ref "U4") (pin "10") (pinfunction "PD6(AIN0)_10") (pintype "bidirectional"))
    )
    (net (code "57") (name "RESET") (class "Default")
      (node (ref "C1") (pin "2") (pinfunction "2_2") (pintype "passive"))
      (node (ref "R") (pin "TP") (pinfunction "TP_TP") (pintype "input"))
      (node (ref "RST") (pin "1") (pinfunction "1_1") (pintype "passive"))
      (node (ref "U4") (pin "29") (pinfunction "PC6(/RESET)_29") (pintype "bidirectional"))
      (node (ref "X2") (pin "2") (pinfunction "S_2") (pintype "passive"))
    )
    (net (code "58") (name "RF_N") (class "Default")
      (node (ref "C14") (pin "2") (pinfunction "2_2") (pintype "passive"))
      (node (ref "U2") (pin "17") (pinfunction "RF_N_17") (pintype "bidirectional"))
    )
    (net (code "59") (name "RF_P") (class "Default")
      (node (ref "C13") (pin "2") (pinfunction "2_2") (pintype "passive"))
      (node (ref "U2") (pin "16") (pinfunction "RF_P_16") (pintype "bidirectional"))
    )
    (net (code "60") (name "RXD") (class "Default")
      (node (ref "FTDI") (pin "4") (pinfunction "4_4") (pintype "passive"))
      (node (ref "U4") (pin "30") (pinfunction "PD0(RXD)_30") (pintype "bidirectional"))
    )
    (net (code "61") (name "SCK") (class "Default")
      (node (ref "S") (pin "TP") (pinfunction "TP_TP") (pintype "input"))
      (node (ref "U2") (pin "41") (pinfunction "SPICLK_41") (pintype "input"))
      (node (ref "U4") (pin "17") (pinfunction "PB5(SCK)_17") (pintype "bidirectional"))
    )
    (net (code "62") (name "SCL") (class "Default")
      (node (ref "U4") (pin "28") (pinfunction "PC5(ADC5/SCL)_28") (pintype "bidirectional"))
    )
    (net (code "63") (name "SDA") (class "Default")
      (node (ref "U4") (pin "27") (pinfunction "PC4(ADC4/SDA)_27") (pintype "bidirectional"))
    )
    (net (code "64") (name "SYNC") (class "Default")
      (node (ref "U2") (pin "29") (pinfunction "SYNC/GPIO7_29") (pintype "bidirectional"))
    )
    (net (code "65") (name "TXD") (class "Default")
      (node (ref "FTDI") (pin "5") (pinfunction "5_5") (pintype "passive"))
      (node (ref "U4") (pin "31") (pinfunction "PD1(TXD)_31") (pintype "bidirectional"))
    )
    (net (code "66") (name "VBAT") (class "Default")
      (node (ref "C22") (pin "1") (pinfunction "1_1") (pintype "passive"))
      (node (ref "C32") (pin "1") (pinfunction "1_1") (pintype "passive"))
      (node (ref "L4") (pin "1") (pinfunction "1_1") (pintype "passive"))
      (node (ref "U1") (pin "P$1") (pinfunction "VOUT1_P$1") (pintype "bidirectional"))
      (node (ref "U1") (pin "P$20") (pinfunction "VOUT2_P$20") (pintype "bidirectional"))
      (node (ref "U3") (pin "11") (pinfunction "EN_11") (pintype "input"))
      (node (ref "U3") (pin "8") (pinfunction "VBAT_8") (pintype "input"))
    )
    (net (code "67") (name "VBUS") (class "Default")
      (node (ref "C6") (pin "1") (pinfunction "1_1") (pintype "passive"))
      (node (ref "CHRG/LBO") (pin "A") (pinfunction "A_A") (pintype "passive"))
      (node (ref "CN4") (pin "VBUS") (pinfunction "VBUS_VBUS") (pintype "power_in"))
      (node (ref "DONE") (pin "A") (pinfunction "A_A") (pintype "passive"))
      (node (ref "R13") (pin "2") (pinfunction "2_2") (pintype "passive"))
      (node (ref "U1") (pin "P$17") (pinfunction "CE_P$17") (pintype "bidirectional"))
      (node (ref "U1") (pin "P$18") (pinfunction "VIN1_P$18") (pintype "bidirectional"))
      (node (ref "U1") (pin "P$19") (pinfunction "VIN2_P$19") (pintype "bidirectional"))
      (node (ref "U1") (pin "P$3") (pinfunction "SEL_P$3") (pintype "bidirectional"))
      (node (ref "U1") (pin "P$4") (pinfunction "PROG2_P$4") (pintype "bidirectional"))
      (node (ref "U1") (pin "P$9") (pinfunction "/TE_P$9") (pintype "bidirectional"))
    )
    (net (code "68") (name "VCOTUNE") (class "Default")
      (node (ref "C15") (pin "2") (pinfunction "2_2") (pintype "passive"))
      (node (ref "R10") (pin "2") (pinfunction "2_2") (pintype "passive"))
      (node (ref "U2") (pin "12") (pinfunction "VCOTUNE_12") (pintype "bidirectional"))
    )
    (net (code "69") (name "VDDCLK") (class "Default")
      (node (ref "C18") (pin "1") (pinfunction "1_1") (pintype "passive"))
      (node (ref "C19") (pin "1") (pinfunction "1_1") (pintype "passive"))
      (node (ref "C7") (pin "1") (pinfunction "1_1") (pintype "passive"))
      (node (ref "U2") (pin "9") (pinfunction "VDDCLK_9") (pintype "power_in"))
    )
    (net (code "70") (name "VDDIF") (class "Default")
      (node (ref "C9") (pin "1") (pinfunction "1_1") (pintype "passive"))
      (node (ref "U2") (pin "7") (pinfunction "VDDIF_7") (pintype "power_in"))
    )
    (net (code "71") (name "VDDIO") (class "Default")
      (node (ref "C20") (pin "2") (pinfunction "2_2") (pintype "passive"))
      (node (ref "C4") (pin "1") (pinfunction "1_1") (pintype "passive"))
      (node (ref "R8") (pin "1") (pinfunction "1_1") (pintype "passive"))
      (node (ref "R9") (pin "1") (pinfunction "1_1") (pintype "passive"))
      (node (ref "TP3-OTP") (pin "P$1") (pinfunction "1_P$1") (pintype "bidirectional"))
      (node (ref "U2") (pin "31") (pinfunction "VDDIO_31") (pintype "power_in"))
      (node (ref "U2") (pin "42") (pinfunction "VDDIO_42") (pintype "power_in"))
    )
    (net (code "72") (name "VDDMS") (class "Default")
      (node (ref "C8") (pin "1") (pinfunction "1_1") (pintype "passive"))
      (node (ref "U2") (pin "6") (pinfunction "VDDMS_6") (pintype "power_in"))
    )
    (net (code "73") (name "VDDPA1") (class "Default")
      (node (ref "C23") (pin "1") (pinfunction "1_1") (pintype "passive"))
      (node (ref "C24") (pin "1") (pinfunction "1_1") (pintype "passive"))
      (node (ref "C25") (pin "1") (pinfunction "1_1") (pintype "passive"))
      (node (ref "L1") (pin "1") (pinfunction "1_1") (pintype "passive"))
      (node (ref "U2") (pin "18") (pinfunction "VDDPA1_18") (pintype "power_in"))
    )
    (net (code "74") (name "VDDPA2") (class "Default")
      (node (ref "C27") (pin "1") (pinfunction "1_1") (pintype "passive"))
      (node (ref "C28") (pin "1") (pinfunction "1_1") (pintype "passive"))
      (node (ref "C29") (pin "1") (pinfunction "1_1") (pintype "passive"))
      (node (ref "C31") (pin "1") (pinfunction "1_1") (pintype "passive"))
      (node (ref "L2") (pin "1") (pinfunction "1_1") (pintype "passive"))
      (node (ref "U2") (pin "19") (pinfunction "VDDPA2_19") (pintype "power_in"))
    )
    (net (code "75") (name "VDDSYN") (class "Default")
      (node (ref "C12") (pin "1") (pinfunction "1_1") (pintype "passive"))
      (node (ref "U2") (pin "10") (pinfunction "VDDSYN_10") (pintype "power_in"))
    )
    (net (code "76") (name "VDDVCO") (class "Default")
      (node (ref "C11") (pin "1") (pinfunction "1_1") (pintype "passive"))
      (node (ref "C15") (pin "1") (pinfunction "1_1") (pintype "passive"))
      (node (ref "C16") (pin "1") (pinfunction "1_1") (pintype "passive"))
      (node (ref "U2") (pin "11") (pinfunction "VDDVCO_11") (pintype "power_in"))
    )
    (net (code "77") (name "VLIPO") (class "Default")
      (node (ref "B2") (pin "2") (pinfunction "+_2") (pintype "passive"))
      (node (ref "C17") (pin "1") (pinfunction "1_1") (pintype "passive"))
      (node (ref "U1") (pin "P$14") (pinfunction "VBAT1_P$14") (pintype "bidirectional"))
      (node (ref "U1") (pin "P$15") (pinfunction "VBAT2_P$15") (pintype "bidirectional"))
      (node (ref "U1") (pin "P$16") (pinfunction "VBATSENS_P$16") (pintype "bidirectional"))
    )
    (net (code "78") (name "VREF") (class "Default")
      (node (ref "R6") (pin "2") (pinfunction "2_2") (pintype "passive"))
      (node (ref "U2") (pin "5") (pinfunction "VREF_5") (pintype "bidirectional"))
    )
    (net (code "79") (name "WAKEUP") (class "Default")
      (node (ref "R4") (pin "1") (pinfunction "1_1") (pintype "passive"))
      (node (ref "U2") (pin "23") (pinfunction "WAKEUP_23") (pintype "input"))
      (node (ref "U4") (pin "11") (pinfunction "PD7(AIN1)_11") (pintype "bidirectional"))
    )
    (net (code "80") (name "unconnected-(CN4-PadD+)") (class "Default")
      (node (ref "CN4") (pin "D+") (pinfunction "D+_D+") (pintype "bidirectional"))
    )
    (net (code "81") (name "unconnected-(CN4-PadD-)") (class "Default")
      (node (ref "CN4") (pin "D-") (pinfunction "D-_D-") (pintype "bidirectional"))
    )
    (net (code "82") (name "unconnected-(CN4-PadID)") (class "Default")
      (node (ref "CN4") (pin "ID") (pinfunction "ID_ID") (pintype "bidirectional"))
    )
    (net (code "83") (name "unconnected-(U1-{slash}PG-PadP$6)") (class "Default")
      (node (ref "U1") (pin "P$6") (pinfunction "/PG_P$6") (pintype "bidirectional"))
    )
    (net (code "84") (name "unconnected-(U2-XTAL2-Pad4)") (class "Default")
      (node (ref "U2") (pin "4") (pinfunction "XTAL2_4") (pintype "input"))
    )
    (net (code "85") (name "unconnected-(U3-LBO-Pad12)") (class "Default")
      (node (ref "U3") (pin "12") (pinfunction "LBO_12") (pintype "output"))
    )
    (net (code "86") (name "~{RST}") (class "Default")
      (node (ref "SJ1") (pin "2") (pinfunction "2_2") (pintype "passive"))
      (node (ref "U2") (pin "27") (pinfunction "~{RST}_27") (pintype "bidirectional"))
    )
    (net (code "87") (name "~{SPICS}") (class "Default")
      (node (ref "U2") (pin "24") (pinfunction "~{SPICS}_24") (pintype "input"))
      (node (ref "U4") (pin "14") (pinfunction "PB2(SS/OC1B)_14") (pintype "bidirectional"))
    )
  )
)
